# MM2_plates.net
KiCad netlist of a schematic drawn in EAGLE
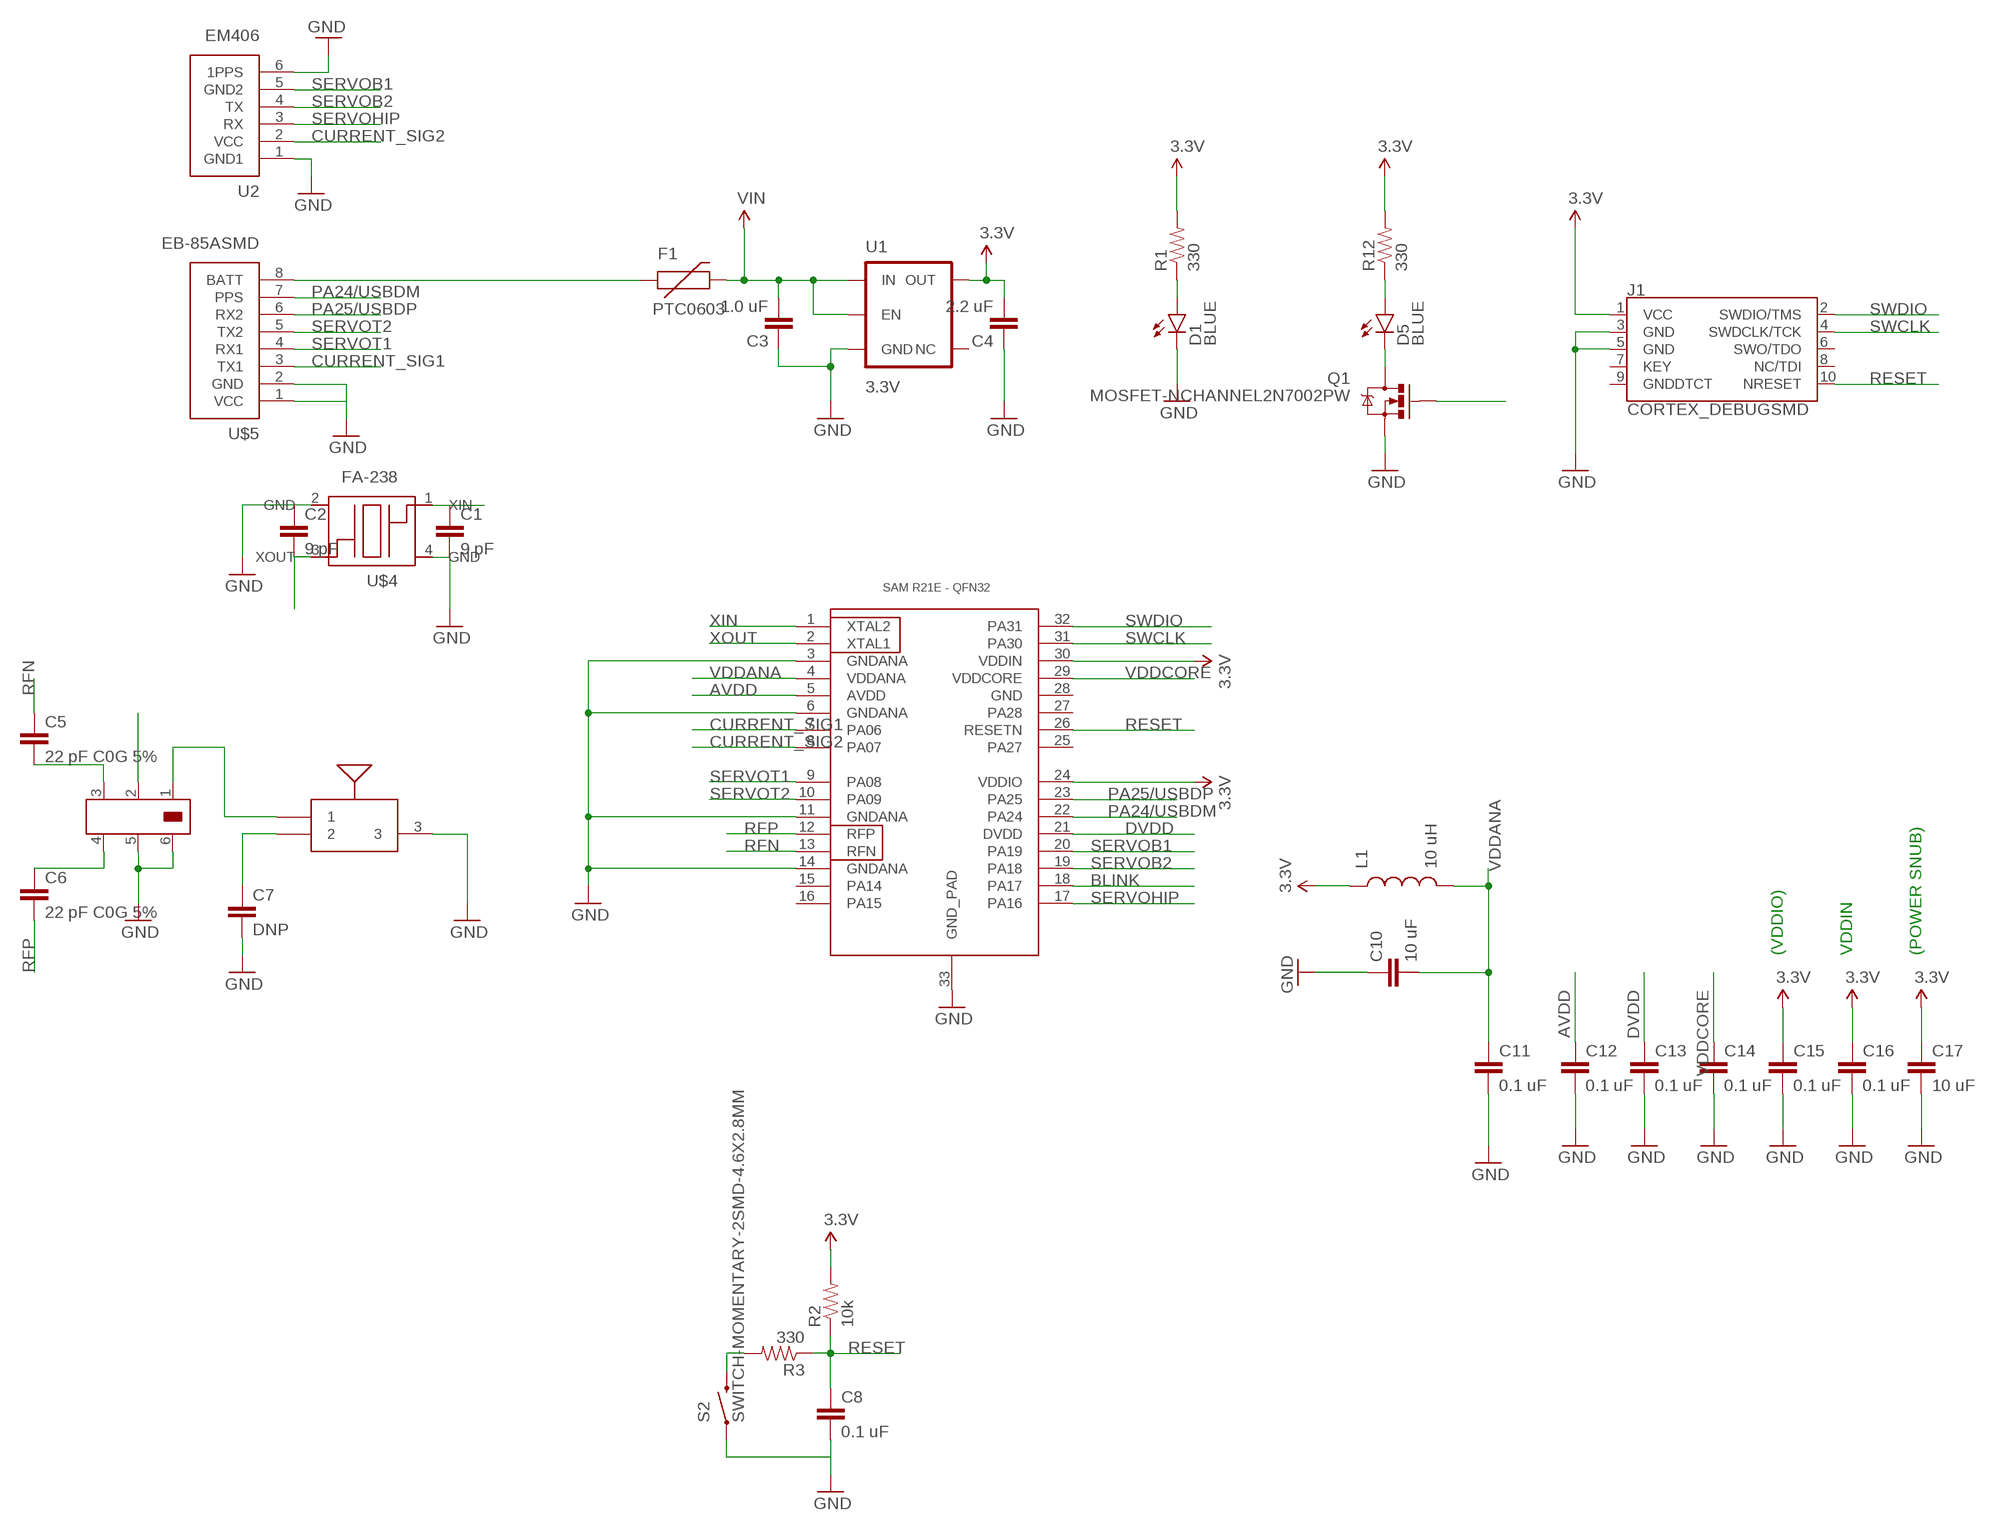
[diagram p0: schematic, sheet 1, part 1 of 2]
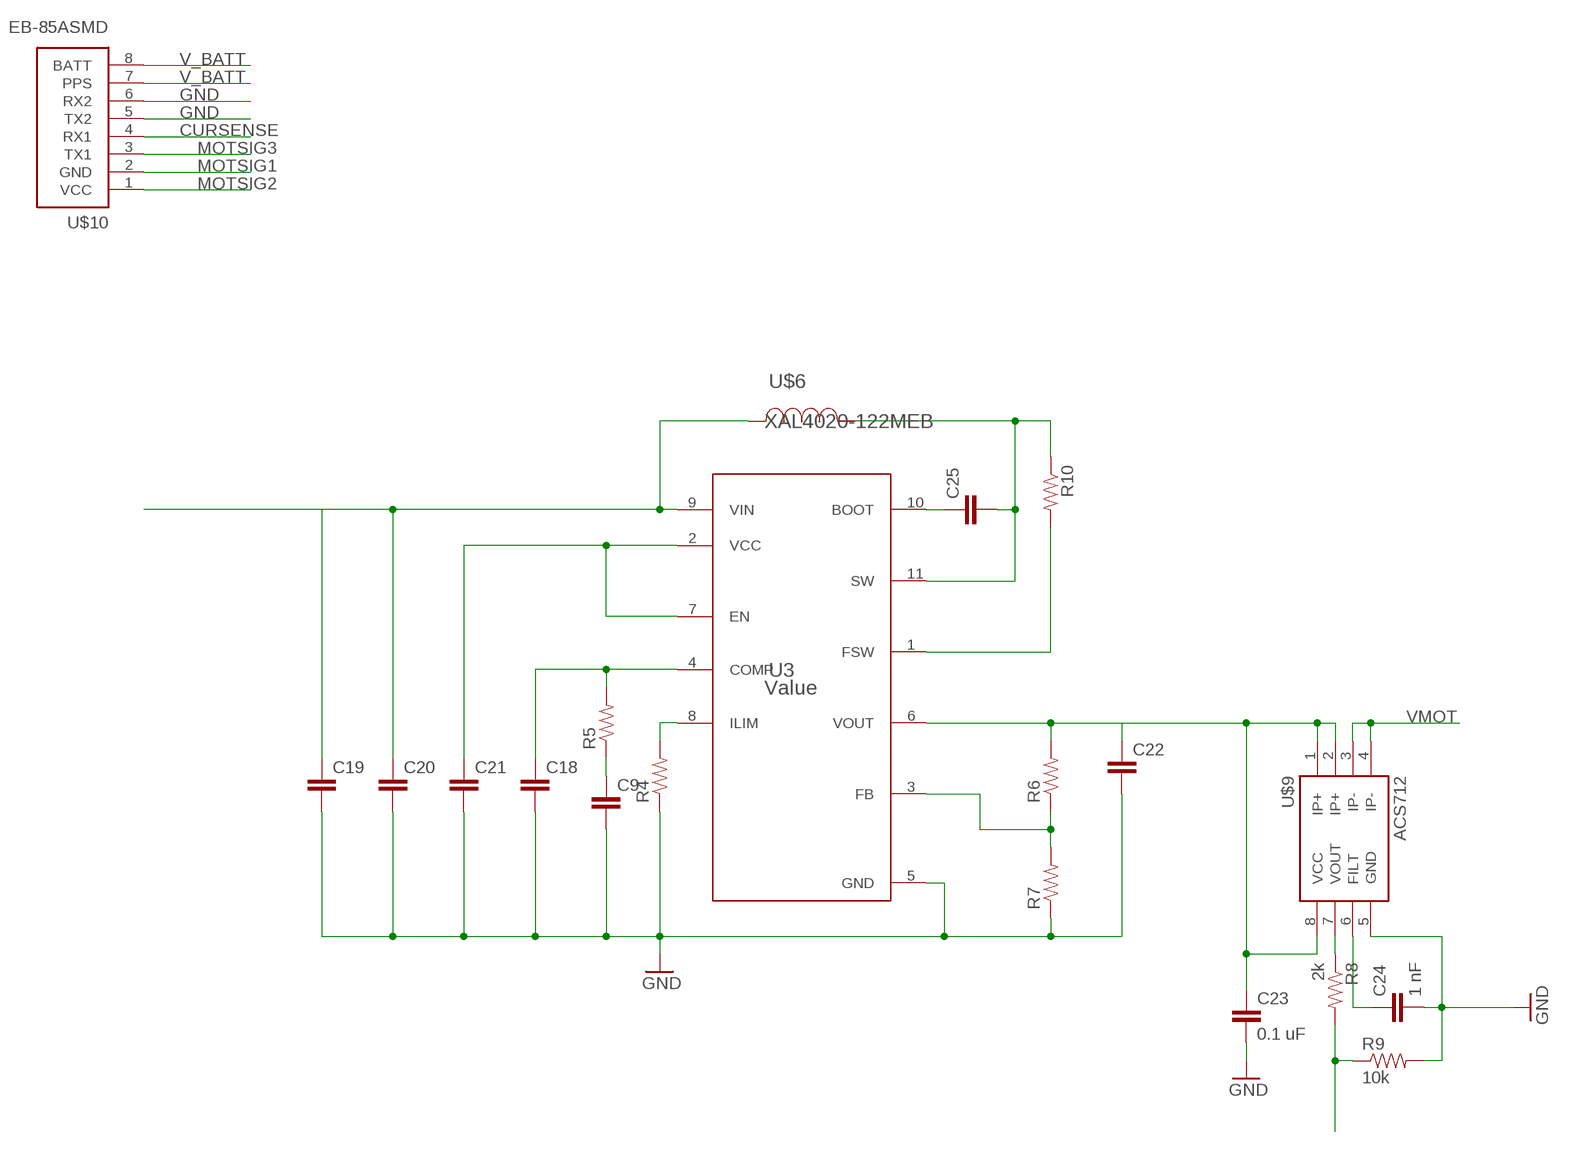
[diagram p1: schematic, sheet 1, part 2 of 2]

(export (version "E")
  (design (tool "Eeschema 10.0.6"))
  (components
    (comp (ref "C1")
      (value "9 pF")
      (footprint "eagle-import:0402-CAP")
      (libsource (lib "eagle-import") (part "CAP0402-CAP"))
    )
    (comp (ref "C2")
      (value "9 pF")
      (footprint "eagle-import:0402-CAP")
      (libsource (lib "eagle-import") (part "CAP0402-CAP"))
    )
    (comp (ref "C3")
      (value "1.0 uF")
      (footprint "eagle-import:0402-CAP")
      (libsource (lib "eagle-import") (part "CAP0402-CAP"))
    )
    (comp (ref "C4")
      (value "2.2 uF")
      (footprint "eagle-import:0402-CAP")
      (libsource (lib "eagle-import") (part "CAP0402-CAP"))
    )
    (comp (ref "C5")
      (value "22 pF C0G 5%")
      (footprint "eagle-import:0402-CAP")
      (libsource (lib "eagle-import") (part "CAP0402-CAP"))
    )
    (comp (ref "C6")
      (value "22 pF C0G 5%")
      (footprint "eagle-import:0402-CAP")
      (libsource (lib "eagle-import") (part "CAP0402-CAP"))
    )
    (comp (ref "C7")
      (value "DNP")
      (footprint "eagle-import:0402-CAP")
      (libsource (lib "eagle-import") (part "CAP0402-CAP"))
    )
    (comp (ref "C8")
      (value "0.1 uF")
      (footprint "eagle-import:0402-CAP")
      (libsource (lib "eagle-import") (part "CAP0402-CAP"))
    )
    (comp (ref "C9")
      (value "CAP0805")
      (footprint "eagle-import:0805")
      (libsource (lib "eagle-import") (part "CAP0805"))
    )
    (comp (ref "C10")
      (value "10 uF")
      (footprint "eagle-import:0402-CAP")
      (libsource (lib "eagle-import") (part "CAP0402-CAP"))
    )
    (comp (ref "C11")
      (value "0.1 uF")
      (footprint "eagle-import:0402-CAP")
      (libsource (lib "eagle-import") (part "CAP0402-CAP"))
    )
    (comp (ref "C12")
      (value "0.1 uF")
      (footprint "eagle-import:0402-CAP")
      (libsource (lib "eagle-import") (part "CAP0402-CAP"))
    )
    (comp (ref "C13")
      (value "0.1 uF")
      (footprint "eagle-import:0402-CAP")
      (libsource (lib "eagle-import") (part "CAP0402-CAP"))
    )
    (comp (ref "C14")
      (value "0.1 uF")
      (footprint "eagle-import:0402-CAP")
      (libsource (lib "eagle-import") (part "CAP0402-CAP"))
    )
    (comp (ref "C15")
      (value "0.1 uF")
      (footprint "eagle-import:0402-CAP")
      (libsource (lib "eagle-import") (part "CAP0402-CAP"))
    )
    (comp (ref "C16")
      (value "0.1 uF")
      (footprint "eagle-import:0402-CAP")
      (libsource (lib "eagle-import") (part "CAP0402-CAP"))
    )
    (comp (ref "C17")
      (value "10 uF")
      (footprint "eagle-import:0402-CAP")
      (libsource (lib "eagle-import") (part "CAP0402-CAP"))
    )
    (comp (ref "C18")
      (value "CAP0805")
      (footprint "eagle-import:0805")
      (libsource (lib "eagle-import") (part "CAP0805"))
    )
    (comp (ref "C19")
      (value "CAP1206")
      (footprint "eagle-import:1206")
      (libsource (lib "eagle-import") (part "CAP1206"))
    )
    (comp (ref "C20")
      (value "CAP0402-CAP")
      (footprint "eagle-import:0402-CAP")
      (libsource (lib "eagle-import") (part "CAP0402-CAP"))
    )
    (comp (ref "C21")
      (value "CAP0603-CAP")
      (footprint "eagle-import:0603-CAP")
      (libsource (lib "eagle-import") (part "CAP0603-CAP"))
    )
    (comp (ref "C22")
      (value "CAP1206")
      (footprint "eagle-import:1206")
      (libsource (lib "eagle-import") (part "CAP1206"))
    )
    (comp (ref "C23")
      (value "0.1 uF")
      (footprint "eagle-import:0402-CAP")
      (libsource (lib "eagle-import") (part "CAP0402-CAP"))
    )
    (comp (ref "C24")
      (value "1 nF")
      (footprint "eagle-import:0402-CAP")
      (libsource (lib "eagle-import") (part "CAP0402-CAP"))
    )
    (comp (ref "C25")
      (value "CAP0402-CAP")
      (footprint "eagle-import:0402-CAP")
      (libsource (lib "eagle-import") (part "CAP0402-CAP"))
    )
    (comp (ref "D1")
      (value "BLUE")
      (footprint "eagle-import:LED-0603")
      (libsource (lib "eagle-import") (part "LED-BLUE0603"))
    )
    (comp (ref "D5")
      (value "BLUE")
      (footprint "eagle-import:LED-0603")
      (libsource (lib "eagle-import") (part "LED-BLUE0603"))
    )
    (comp (ref "F1")
      (value "PTC0603")
      (footprint "eagle-import:0603")
      (libsource (lib "eagle-import") (part "PTC0603"))
    )
    (comp (ref "J1")
      (value "CORTEX_DEBUGSMD")
      (footprint "eagle-import:SAMTECH_FTSH-105-01")
      (libsource (lib "eagle-import") (part "CORTEX_DEBUGSMD"))
    )
    (comp (ref "L1")
      (value "10 uH")
      (footprint "eagle-import:0603")
      (libsource (lib "eagle-import") (part "INDUCTOR0603"))
    )
    (comp (ref "Q1")
      (value "MOSFET-NCHANNEL2N7002PW")
      (footprint "eagle-import:SOT323")
      (libsource (lib "eagle-import") (part "MOSFET-NCHANNEL2N7002PW"))
    )
    (comp (ref "R1")
      (value "330")
      (footprint "eagle-import:0402-RES")
      (libsource (lib "eagle-import") (part "RESISTOR0402-RES"))
    )
    (comp (ref "R2")
      (value "10k")
      (footprint "eagle-import:0402-RES")
      (libsource (lib "eagle-import") (part "RESISTOR0402-RES"))
    )
    (comp (ref "R3")
      (value "330")
      (footprint "eagle-import:0402-RES")
      (libsource (lib "eagle-import") (part "RESISTOR0402-RES"))
    )
    (comp (ref "R4")
      (value "RESISTOR1206")
      (footprint "eagle-import:1206")
      (libsource (lib "eagle-import") (part "SparkFun-Resistors_RESISTOR1206"))
    )
    (comp (ref "R5")
      (value "RESISTOR0402")
      (footprint "eagle-import:0402-RES")
      (libsource (lib "eagle-import") (part "RESISTOR0402"))
    )
    (comp (ref "R6")
      (value "RESISTOR0402")
      (footprint "eagle-import:0402-RES")
      (libsource (lib "eagle-import") (part "RESISTOR0402"))
    )
    (comp (ref "R7")
      (value "RESISTOR0603-RES")
      (footprint "eagle-import:0603-RES")
      (libsource (lib "eagle-import") (part "RESISTOR0603-RES"))
    )
    (comp (ref "R8")
      (value "2k")
      (footprint "eagle-import:0402-RES")
      (libsource (lib "eagle-import") (part "RESISTOR0402-RES"))
    )
    (comp (ref "R9")
      (value "10k")
      (footprint "eagle-import:0402-RES")
      (libsource (lib "eagle-import") (part "RESISTOR0402-RES"))
    )
    (comp (ref "R10")
      (value "RESISTOR1206")
      (footprint "eagle-import:1206")
      (libsource (lib "eagle-import") (part "SparkFun-Resistors_RESISTOR1206"))
    )
    (comp (ref "R12")
      (value "330")
      (footprint "eagle-import:0402-RES")
      (libsource (lib "eagle-import") (part "RESISTOR0402-RES"))
    )
    (comp (ref "S2")
      (value "SWITCH-MOMENTARY-2SMD-4.6X2.8MM")
      (footprint "eagle-import:TACTILE_SWITCH_SMD_4.6X2.8MM")
      (libsource (lib "eagle-import") (part "SWITCH-MOMENTARY-2SMD-4.6X2.8MM"))
    )
    (comp (ref "U$1")
      (value "ATSAMR21E18A-MUT")
      (footprint "eagle-import:QFN32")
      (libsource (lib "eagle-import") (part "ATSAMR21E18A-MUT"))
    )
    (comp (ref "U$2")
      (value "JOHANSON_2450BM15A0015E")
      (footprint "eagle-import:0805_BALUN")
      (libsource (lib "eagle-import") (part "JOHANSON_2450BM15A0015E"))
    )
    (comp (ref "U$3")
      (value "PULSE_ANT_2.4GHZ")
      (footprint "eagle-import:ANT_BAR")
      (libsource (lib "eagle-import") (part "PULSE_ANT_2.4GHZ"))
    )
    (comp (ref "U$4")
      (value "FA-238")
      (footprint "eagle-import:FA-238")
      (libsource (lib "eagle-import") (part "FA-238"))
    )
    (comp (ref "U$5")
      (value "EB-85ASMD")
      (footprint "eagle-import:EB-85A")
      (libsource (lib "eagle-import") (part "EB-85ASMD"))
    )
    (comp (ref "U$6")
      (value "XAL4020-122MEB")
      (footprint "eagle-import:XAL4020")
      (libsource (lib "eagle-import") (part "XAL4020-122MEB"))
    )
    (comp (ref "U$9")
      (value "ACS712")
      (footprint "eagle-import:SO08")
      (libsource (lib "eagle-import") (part "ACS712"))
    )
    (comp (ref "U$10")
      (value "EB-85ASMD")
      (footprint "eagle-import:EB-85A")
      (libsource (lib "eagle-import") (part "EB-85ASMD"))
    )
    (comp (ref "U1")
      (value "3.3V")
      (footprint "eagle-import:SOT23-5")
      (libsource (lib "eagle-import") (part "V_REG_AP2112K-3.3V"))
    )
    (comp (ref "U2")
      (value "EM406")
      (footprint "eagle-import:EM406")
      (libsource (lib "eagle-import") (part "EM406"))
    )
    (comp (ref "U3")
      (value "Value")
      (footprint "eagle-import:RNR0011A")
      (fields
        (field (name "MANUFACTURER") "Texas Instruments")
        (field (name "MANUFACTURER_PART_NUMBER") "TPS61089RNRR")
      )
      (libsource (lib "eagle-import") (part "TPS61089RNRR"))
    )
  )
  (nets
    (net (code "1") (name "/AVDD") (class "Default")
      (node (ref "C12") (pin "1") (pinfunction "1_1") (pintype "passive"))
      (node (ref "U$1") (pin "5") (pinfunction "AVDD_5") (pintype "bidirectional"))
    )
    (net (code "2") (name "/BLINK") (class "Default")
      (node (ref "Q1") (pin "1") (pinfunction "G_1") (pintype "passive"))
      (node (ref "U$1") (pin "18") (pinfunction "PA17_18") (pintype "bidirectional"))
    )
    (net (code "3") (name "/CURRENT_SIG1") (class "Default")
      (node (ref "U$1") (pin "7") (pinfunction "PA06_7") (pintype "bidirectional"))
      (node (ref "U$5") (pin "3") (pinfunction "TX1_3") (pintype "output"))
    )
    (net (code "4") (name "/CURRENT_SIG2") (class "Default")
      (node (ref "U$1") (pin "8") (pinfunction "PA07_8") (pintype "bidirectional"))
      (node (ref "U2") (pin "2") (pinfunction "VCC_2") (pintype "bidirectional"))
    )
    (net (code "5") (name "/CURSENSE") (class "Default")
      (node (ref "R8") (pin "2") (pinfunction "2_2") (pintype "passive"))
      (node (ref "R9") (pin "1") (pinfunction "1_1") (pintype "passive"))
      (node (ref "U$10") (pin "4") (pinfunction "RX1_4") (pintype "input"))
    )
    (net (code "6") (name "/DVDD") (class "Default")
      (node (ref "C13") (pin "1") (pinfunction "1_1") (pintype "passive"))
      (node (ref "U$1") (pin "21") (pinfunction "DVDD_21") (pintype "bidirectional"))
    )
    (net (code "7") (name "/MOTSIG1") (class "Default")
      (node (ref "U$10") (pin "2") (pinfunction "GND_2") (pintype "power_in"))
    )
    (net (code "8") (name "/MOTSIG2") (class "Default")
      (node (ref "U$10") (pin "1") (pinfunction "VCC_1") (pintype "power_in"))
    )
    (net (code "9") (name "/MOTSIG3") (class "Default")
      (node (ref "U$10") (pin "3") (pinfunction "TX1_3") (pintype "output"))
    )
    (net (code "10") (name "/PA24{slash}USBDM") (class "Default")
      (node (ref "U$1") (pin "22") (pinfunction "PA24_22") (pintype "bidirectional"))
      (node (ref "U$5") (pin "7") (pinfunction "PPS_7") (pintype "output"))
    )
    (net (code "11") (name "/PA25{slash}USBDP") (class "Default")
      (node (ref "U$1") (pin "23") (pinfunction "PA25_23") (pintype "bidirectional"))
      (node (ref "U$5") (pin "6") (pinfunction "RX2_6") (pintype "input"))
    )
    (net (code "12") (name "/RESET") (class "Default")
      (node (ref "C8") (pin "1") (pinfunction "1_1") (pintype "passive"))
      (node (ref "J1") (pin "10") (pinfunction "NRESET_10") (pintype "bidirectional"))
      (node (ref "R2") (pin "1") (pinfunction "1_1") (pintype "passive"))
      (node (ref "R3") (pin "1") (pinfunction "1_1") (pintype "passive"))
      (node (ref "U$1") (pin "26") (pinfunction "RESETN_26") (pintype "bidirectional"))
    )
    (net (code "13") (name "/RFN") (class "Default")
      (node (ref "C5") (pin "1") (pinfunction "1_1") (pintype "passive"))
      (node (ref "U$1") (pin "13") (pinfunction "RFN_13") (pintype "bidirectional"))
    )
    (net (code "14") (name "/RFP") (class "Default")
      (node (ref "C6") (pin "2") (pinfunction "2_2") (pintype "passive"))
      (node (ref "U$1") (pin "12") (pinfunction "RFP_12") (pintype "bidirectional"))
    )
    (net (code "15") (name "/SERVOB1") (class "Default")
      (node (ref "U$1") (pin "20") (pinfunction "PA19_20") (pintype "bidirectional"))
      (node (ref "U2") (pin "5") (pinfunction "GND2_5") (pintype "bidirectional"))
    )
    (net (code "16") (name "/SERVOB2") (class "Default")
      (node (ref "U$1") (pin "19") (pinfunction "PA18_19") (pintype "bidirectional"))
      (node (ref "U2") (pin "4") (pinfunction "TX_4") (pintype "bidirectional"))
    )
    (net (code "17") (name "/SERVOHIP") (class "Default")
      (node (ref "U$1") (pin "17") (pinfunction "PA16_17") (pintype "bidirectional"))
      (node (ref "U2") (pin "3") (pinfunction "RX_3") (pintype "bidirectional"))
    )
    (net (code "18") (name "/SERVOT1") (class "Default")
      (node (ref "U$1") (pin "9") (pinfunction "PA08_9") (pintype "bidirectional"))
      (node (ref "U$5") (pin "4") (pinfunction "RX1_4") (pintype "input"))
    )
    (net (code "19") (name "/SERVOT2") (class "Default")
      (node (ref "U$1") (pin "10") (pinfunction "PA09_10") (pintype "bidirectional"))
      (node (ref "U$5") (pin "5") (pinfunction "TX2_5") (pintype "output"))
    )
    (net (code "20") (name "/SWCLK") (class "Default")
      (node (ref "J1") (pin "4") (pinfunction "SWDCLK/TCK_4") (pintype "bidirectional"))
      (node (ref "U$1") (pin "31") (pinfunction "PA30_31") (pintype "bidirectional"))
    )
    (net (code "21") (name "/SWDIO") (class "Default")
      (node (ref "J1") (pin "2") (pinfunction "SWDIO/TMS_2") (pintype "bidirectional"))
      (node (ref "U$1") (pin "32") (pinfunction "PA31_32") (pintype "bidirectional"))
    )
    (net (code "22") (name "/VDDANA") (class "Default")
      (node (ref "C10") (pin "2") (pinfunction "2_2") (pintype "passive"))
      (node (ref "C11") (pin "1") (pinfunction "1_1") (pintype "passive"))
      (node (ref "L1") (pin "2") (pinfunction "2_2") (pintype "passive"))
      (node (ref "U$1") (pin "4") (pinfunction "VDDANA_4") (pintype "bidirectional"))
    )
    (net (code "23") (name "/VDDCORE") (class "Default")
      (node (ref "C14") (pin "1") (pinfunction "1_1") (pintype "passive"))
      (node (ref "U$1") (pin "29") (pinfunction "VDDCORE_29") (pintype "bidirectional"))
    )
    (net (code "24") (name "/VMOT") (class "Default")
      (node (ref "U$9") (pin "3") (pinfunction "IP-_3") (pintype "bidirectional"))
      (node (ref "U$9") (pin "4") (pinfunction "IP-_4") (pintype "bidirectional"))
    )
    (net (code "25") (name "/V_BATT") (class "Default")
      (node (ref "C19") (pin "1") (pinfunction "1_1") (pintype "passive"))
      (node (ref "C20") (pin "1") (pinfunction "1_1") (pintype "passive"))
      (node (ref "U$10") (pin "7") (pinfunction "PPS_7") (pintype "output"))
      (node (ref "U$10") (pin "8") (pinfunction "BATT_8") (pintype "power_in"))
      (node (ref "U$6") (pin "1") (pinfunction "1_1") (pintype "passive"))
      (node (ref "U3") (pin "9") (pinfunction "VIN_9") (pintype "power_in"))
    )
    (net (code "26") (name "/XIN") (class "Default")
      (node (ref "C1") (pin "1") (pinfunction "1_1") (pintype "passive"))
      (node (ref "U$1") (pin "1") (pinfunction "XTAL2_1") (pintype "bidirectional"))
      (node (ref "U$4") (pin "1") (pinfunction "XIN_1") (pintype "bidirectional"))
    )
    (net (code "27") (name "/XOUT") (class "Default")
      (node (ref "C2") (pin "2") (pinfunction "2_2") (pintype "passive"))
      (node (ref "U$1") (pin "2") (pinfunction "XTAL1_2") (pintype "bidirectional"))
      (node (ref "U$4") (pin "3") (pinfunction "XOUT_3") (pintype "bidirectional"))
    )
    (net (code "28") (name "3.3V") (class "Default")
      (node (ref "C15") (pin "1") (pinfunction "1_1") (pintype "passive"))
      (node (ref "C16") (pin "1") (pinfunction "1_1") (pintype "passive"))
      (node (ref "C17") (pin "1") (pinfunction "1_1") (pintype "passive"))
      (node (ref "C4") (pin "2") (pinfunction "2_2") (pintype "passive"))
      (node (ref "J1") (pin "1") (pinfunction "VCC_1") (pintype "bidirectional"))
      (node (ref "L1") (pin "1") (pinfunction "1_1") (pintype "passive"))
      (node (ref "R1") (pin "2") (pinfunction "2_2") (pintype "passive"))
      (node (ref "R12") (pin "2") (pinfunction "2_2") (pintype "passive"))
      (node (ref "R2") (pin "2") (pinfunction "2_2") (pintype "passive"))
      (node (ref "U$1") (pin "24") (pinfunction "VDDIO_24") (pintype "bidirectional"))
      (node (ref "U$1") (pin "30") (pinfunction "VDDIN_30") (pintype "bidirectional"))
      (node (ref "U1") (pin "5") (pinfunction "OUT_5") (pintype "passive"))
    )
    (net (code "29") (name "GND") (class "Default")
      (node (ref "C1") (pin "2") (pinfunction "2_2") (pintype "passive"))
      (node (ref "C10") (pin "1") (pinfunction "1_1") (pintype "passive"))
      (node (ref "C11") (pin "2") (pinfunction "2_2") (pintype "passive"))
      (node (ref "C12") (pin "2") (pinfunction "2_2") (pintype "passive"))
      (node (ref "C13") (pin "2") (pinfunction "2_2") (pintype "passive"))
      (node (ref "C14") (pin "2") (pinfunction "2_2") (pintype "passive"))
      (node (ref "C15") (pin "2") (pinfunction "2_2") (pintype "passive"))
      (node (ref "C16") (pin "2") (pinfunction "2_2") (pintype "passive"))
      (node (ref "C17") (pin "2") (pinfunction "2_2") (pintype "passive"))
      (node (ref "C18") (pin "2") (pinfunction "2_2") (pintype "passive"))
      (node (ref "C19") (pin "2") (pinfunction "2_2") (pintype "passive"))
      (node (ref "C2") (pin "1") (pinfunction "1_1") (pintype "passive"))
      (node (ref "C20") (pin "2") (pinfunction "2_2") (pintype "passive"))
      (node (ref "C21") (pin "2") (pinfunction "2_2") (pintype "passive"))
      (node (ref "C22") (pin "2") (pinfunction "2_2") (pintype "passive"))
      (node (ref "C23") (pin "2") (pinfunction "2_2") (pintype "passive"))
      (node (ref "C24") (pin "2") (pinfunction "2_2") (pintype "passive"))
      (node (ref "C3") (pin "1") (pinfunction "1_1") (pintype "passive"))
      (node (ref "C4") (pin "1") (pinfunction "1_1") (pintype "passive"))
      (node (ref "C7") (pin "2") (pinfunction "2_2") (pintype "passive"))
      (node (ref "C8") (pin "2") (pinfunction "2_2") (pintype "passive"))
      (node (ref "C9") (pin "2") (pinfunction "2_2") (pintype "passive"))
      (node (ref "D1") (pin "C") (pinfunction "C_C") (pintype "passive"))
      (node (ref "J1") (pin "3") (pinfunction "GND_3") (pintype "bidirectional"))
      (node (ref "J1") (pin "5") (pinfunction "GND_5") (pintype "bidirectional"))
      (node (ref "Q1") (pin "2") (pinfunction "S_2") (pintype "passive"))
      (node (ref "R4") (pin "1") (pinfunction "1_1") (pintype "passive"))
      (node (ref "R7") (pin "1") (pinfunction "1_1") (pintype "passive"))
      (node (ref "R9") (pin "2") (pinfunction "2_2") (pintype "passive"))
      (node (ref "S2") (pin "1") (pinfunction "1_1") (pintype "passive"))
      (node (ref "S2") (pin "2") (pinfunction "1_2") (pintype "passive"))
      (node (ref "U$1") (pin "11") (pinfunction "GNDANA_11") (pintype "bidirectional"))
      (node (ref "U$1") (pin "14") (pinfunction "GNDANA_14") (pintype "bidirectional"))
      (node (ref "U$1") (pin "3") (pinfunction "GNDANA_3") (pintype "bidirectional"))
      (node (ref "U$1") (pin "33") (pinfunction "GND_PAD_33") (pintype "bidirectional"))
      (node (ref "U$1") (pin "6") (pinfunction "GNDANA_6") (pintype "bidirectional"))
      (node (ref "U$10") (pin "5") (pinfunction "TX2_5") (pintype "output"))
      (node (ref "U$10") (pin "6") (pinfunction "RX2_6") (pintype "input"))
      (node (ref "U$2") (pin "5") (pinfunction "5_5") (pintype "bidirectional"))
      (node (ref "U$2") (pin "6") (pinfunction "6_6") (pintype "bidirectional"))
      (node (ref "U$3") (pin "3") (pinfunction "3_3") (pintype "bidirectional"))
      (node (ref "U$4") (pin "2") (pinfunction "GND_2") (pintype "bidirectional"))
      (node (ref "U$4") (pin "4") (pinfunction "GND_4") (pintype "bidirectional"))
      (node (ref "U$5") (pin "1") (pinfunction "VCC_1") (pintype "power_in"))
      (node (ref "U$5") (pin "2") (pinfunction "GND_2") (pintype "power_in"))
      (node (ref "U$9") (pin "5") (pinfunction "GND_5") (pintype "bidirectional"))
      (node (ref "U1") (pin "2") (pinfunction "GND_2") (pintype "input"))
      (node (ref "U2") (pin "1") (pinfunction "GND1_1") (pintype "bidirectional"))
      (node (ref "U2") (pin "6") (pinfunction "1PPS_6") (pintype "bidirectional"))
      (node (ref "U3") (pin "5") (pinfunction "GND_5") (pintype "power_in"))
    )
    (net (code "30") (name "Net-(C5-Pad2)") (class "Default")
      (node (ref "C5") (pin "2") (pinfunction "2_2") (pintype "passive"))
      (node (ref "U$2") (pin "3") (pinfunction "3_3") (pintype "bidirectional"))
    )
    (net (code "31") (name "Net-(C6-Pad1)") (class "Default")
      (node (ref "C6") (pin "1") (pinfunction "1_1") (pintype "passive"))
      (node (ref "U$2") (pin "4") (pinfunction "4_4") (pintype "bidirectional"))
    )
    (net (code "32") (name "Net-(C7-Pad1)") (class "Default")
      (node (ref "C7") (pin "1") (pinfunction "1_1") (pintype "passive"))
      (node (ref "U$3") (pin "2") (pinfunction "2_2") (pintype "bidirectional"))
    )
    (net (code "33") (name "Net-(C9-Pad1)") (class "Default")
      (node (ref "C9") (pin "1") (pinfunction "1_1") (pintype "passive"))
      (node (ref "R5") (pin "1") (pinfunction "1_1") (pintype "passive"))
    )
    (net (code "34") (name "Net-(D1-PadA)") (class "Default")
      (node (ref "D1") (pin "A") (pinfunction "A_A") (pintype "passive"))
      (node (ref "R1") (pin "1") (pinfunction "1_1") (pintype "passive"))
    )
    (net (code "35") (name "Net-(D5-PadA)") (class "Default")
      (node (ref "D5") (pin "A") (pinfunction "A_A") (pintype "passive"))
      (node (ref "R12") (pin "1") (pinfunction "1_1") (pintype "passive"))
    )
    (net (code "36") (name "Net-(Q1-D)") (class "Default")
      (node (ref "D5") (pin "C") (pinfunction "C_C") (pintype "passive"))
      (node (ref "Q1") (pin "3") (pinfunction "D_3") (pintype "passive"))
    )
    (net (code "37") (name "Net-(R3-Pad2)") (class "Default")
      (node (ref "R3") (pin "2") (pinfunction "2_2") (pintype "passive"))
      (node (ref "S2") (pin "3") (pinfunction "2_3") (pintype "passive"))
      (node (ref "S2") (pin "4") (pinfunction "2_4") (pintype "passive"))
    )
    (net (code "38") (name "Net-(U$2-Pad1)") (class "Default")
      (node (ref "U$2") (pin "1") (pinfunction "1_1") (pintype "bidirectional"))
      (node (ref "U$3") (pin "1") (pinfunction "1_1") (pintype "bidirectional"))
    )
    (net (code "39") (name "Net-(U$5-BATT)") (class "Default")
      (node (ref "F1") (pin "1") (pinfunction "1_1") (pintype "bidirectional"))
      (node (ref "U$5") (pin "8") (pinfunction "BATT_8") (pintype "power_in"))
    )
    (net (code "40") (name "Net-(U$9-FILT)") (class "Default")
      (node (ref "C24") (pin "1") (pinfunction "1_1") (pintype "passive"))
      (node (ref "U$9") (pin "6") (pinfunction "FILT_6") (pintype "bidirectional"))
    )
    (net (code "41") (name "Net-(U$9-VCC)") (class "Default")
      (node (ref "C22") (pin "1") (pinfunction "1_1") (pintype "passive"))
      (node (ref "C23") (pin "1") (pinfunction "1_1") (pintype "passive"))
      (node (ref "R6") (pin "2") (pinfunction "2_2") (pintype "passive"))
      (node (ref "U$9") (pin "1") (pinfunction "IP+_1") (pintype "bidirectional"))
      (node (ref "U$9") (pin "2") (pinfunction "IP+_2") (pintype "bidirectional"))
      (node (ref "U$9") (pin "8") (pinfunction "VCC_8") (pintype "bidirectional"))
      (node (ref "U3") (pin "6") (pinfunction "VOUT_6") (pintype "power_in"))
    )
    (net (code "42") (name "Net-(U$9-VOUT)") (class "Default")
      (node (ref "R8") (pin "1") (pinfunction "1_1") (pintype "passive"))
      (node (ref "U$9") (pin "7") (pinfunction "VOUT_7") (pintype "bidirectional"))
    )
    (net (code "43") (name "Net-(U3-BOOT)") (class "Default")
      (node (ref "C25") (pin "1") (pinfunction "1_1") (pintype "passive"))
      (node (ref "U3") (pin "10") (pinfunction "BOOT_10") (pintype "power_in"))
    )
    (net (code "44") (name "Net-(U3-COMP)") (class "Default")
      (node (ref "C18") (pin "1") (pinfunction "1_1") (pintype "passive"))
      (node (ref "R5") (pin "2") (pinfunction "2_2") (pintype "passive"))
      (node (ref "U3") (pin "4") (pinfunction "COMP_4") (pintype "output"))
    )
    (net (code "45") (name "Net-(U3-EN)") (class "Default")
      (node (ref "C21") (pin "1") (pinfunction "1_1") (pintype "passive"))
      (node (ref "U3") (pin "2") (pinfunction "VCC_2") (pintype "power_in"))
      (node (ref "U3") (pin "7") (pinfunction "EN_7") (pintype "input"))
    )
    (net (code "46") (name "Net-(U3-FB)") (class "Default")
      (node (ref "R6") (pin "1") (pinfunction "1_1") (pintype "passive"))
      (node (ref "R7") (pin "2") (pinfunction "2_2") (pintype "passive"))
      (node (ref "U3") (pin "3") (pinfunction "FB_3") (pintype "input"))
    )
    (net (code "47") (name "Net-(U3-FSW)") (class "Default")
      (node (ref "R10") (pin "2") (pinfunction "2_2") (pintype "passive"))
      (node (ref "U3") (pin "1") (pinfunction "FSW_1") (pintype "input"))
    )
    (net (code "48") (name "Net-(U3-ILIM)") (class "Default")
      (node (ref "R4") (pin "2") (pinfunction "2_2") (pintype "passive"))
      (node (ref "U3") (pin "8") (pinfunction "ILIM_8") (pintype "input"))
    )
    (net (code "49") (name "Net-(U3-SW)") (class "Default")
      (node (ref "C25") (pin "2") (pinfunction "2_2") (pintype "passive"))
      (node (ref "R10") (pin "1") (pinfunction "1_1") (pintype "passive"))
      (node (ref "U$6") (pin "2") (pinfunction "2_2") (pintype "passive"))
      (node (ref "U3") (pin "11") (pinfunction "SW_11") (pintype "power_in"))
    )
    (net (code "50") (name "VIN") (class "Default")
      (node (ref "C3") (pin "2") (pinfunction "2_2") (pintype "passive"))
      (node (ref "F1") (pin "2") (pinfunction "2_2") (pintype "bidirectional"))
      (node (ref "U1") (pin "1") (pinfunction "IN_1") (pintype "input"))
      (node (ref "U1") (pin "3") (pinfunction "EN_3") (pintype "input"))
    )
    (net (code "51") (name "unconnected-(J1-GNDDTCT-Pad9)") (class "Default")
      (node (ref "J1") (pin "9") (pinfunction "GNDDTCT_9") (pintype "bidirectional"))
    )
    (net (code "52") (name "unconnected-(J1-KEY-Pad7)") (class "Default")
      (node (ref "J1") (pin "7") (pinfunction "KEY_7") (pintype "bidirectional"))
    )
    (net (code "53") (name "unconnected-(J1-NC{slash}TDI-Pad8)") (class "Default")
      (node (ref "J1") (pin "8") (pinfunction "NC/TDI_8") (pintype "bidirectional"))
    )
    (net (code "54") (name "unconnected-(J1-SWO{slash}TDO-Pad6)") (class "Default")
      (node (ref "J1") (pin "6") (pinfunction "SWO/TDO_6") (pintype "bidirectional"))
    )
    (net (code "55") (name "unconnected-(U$1-GND-Pad28)") (class "Default")
      (node (ref "U$1") (pin "28") (pinfunction "GND_28") (pintype "bidirectional"))
    )
    (net (code "56") (name "unconnected-(U$1-PA14-Pad15)") (class "Default")
      (node (ref "U$1") (pin "15") (pinfunction "PA14_15") (pintype "bidirectional"))
    )
    (net (code "57") (name "unconnected-(U$1-PA15-Pad16)") (class "Default")
      (node (ref "U$1") (pin "16") (pinfunction "PA15_16") (pintype "bidirectional"))
    )
    (net (code "58") (name "unconnected-(U$1-PA27-Pad25)") (class "Default")
      (node (ref "U$1") (pin "25") (pinfunction "PA27_25") (pintype "bidirectional"))
    )
    (net (code "59") (name "unconnected-(U$1-PA28-Pad27)") (class "Default")
      (node (ref "U$1") (pin "27") (pinfunction "PA28_27") (pintype "bidirectional"))
    )
    (net (code "60") (name "unconnected-(U$2-Pad2)") (class "Default")
      (node (ref "U$2") (pin "2") (pinfunction "2_2") (pintype "bidirectional"))
    )
    (net (code "61") (name "unconnected-(U1-NC-Pad4)") (class "Default")
      (node (ref "U1") (pin "4") (pinfunction "NC_4") (pintype "input"))
    )
  )
)
